# LEDPanel_Dimmer.net
KiCad netlist of a schematic drawn in EAGLE
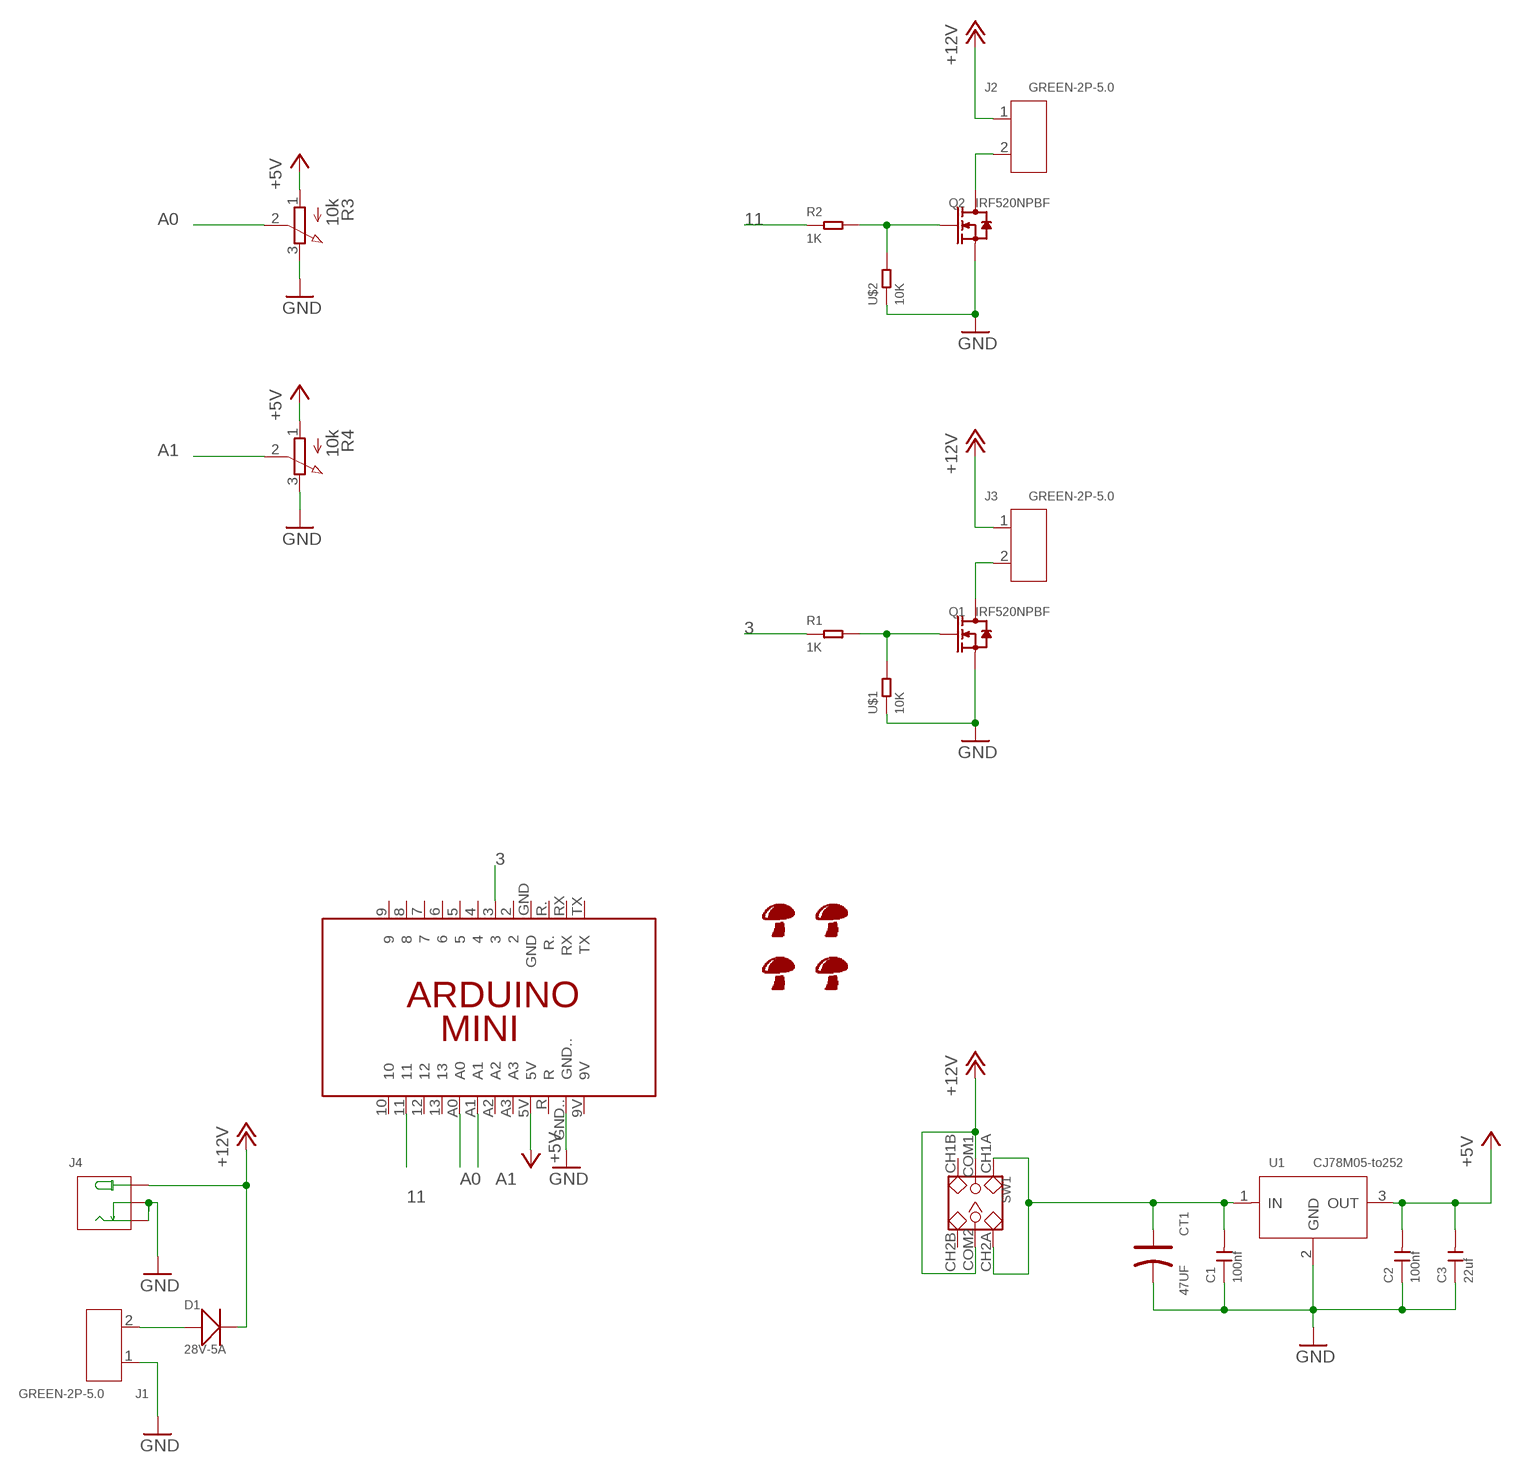
[diagram p0: schematic, sheet 1]

(export (version "E")
  (design (tool "Eeschema 10.0.6"))
  (components
    (comp (ref "C1")
      (value "100nf")
      (footprint "eagle-import:C0805")
      (fields (field (name "MPN") "CC0805KRX7R9BB104"))
      (libsource (lib "eagle-import") (part "CERAMIC-100NF-50V-10%-X7R(0805)"))
    )
    (comp (ref "C2")
      (value "100nf")
      (footprint "eagle-import:C0805")
      (fields (field (name "MPN") "CC0805KRX7R9BB104"))
      (libsource (lib "eagle-import") (part "CERAMIC-100NF-50V-10%-X7R(0805)"))
    )
    (comp (ref "C3")
      (value "22uf")
      (footprint "eagle-import:C0805")
      (fields (field (name "MPN") "CC0805MKX5R5BB226"))
      (libsource (lib "eagle-import") (part "CERAMIC-22UF-6.3V-20%-X5R(0805)"))
    )
    (comp (ref "CT1")
      (value "47UF")
      (footprint "eagle-import:ELECTRO-SMD-C-6MM")
      (fields (field (name "MPN") "CS1E470M-CRE54"))
      (libsource (lib "eagle-import") (part "ALUMINUM-SMD-47UF-25V(D6.3-H5.3MM)"))
    )
    (comp (ref "D1")
      (value "28V-5A")
      (footprint "eagle-import:DO-214AA")
      (fields (field (name "MPN") "SS54B"))
      (libsource (lib "eagle-import") (part "SMD-DIODE-SCHOTTKY-28V-5A(DO-214AA)"))
    )
    (comp (ref "J1")
      (value "GREEN-2P-5.0")
      (footprint "eagle-import:H2-5.0-10.5X8.0MM")
      (libsource (lib "eagle-import") (part "SCREW-TERMINAL-GREEN(2P-5.0)"))
    )
    (comp (ref "J2")
      (value "GREEN-2P-5.0")
      (footprint "eagle-import:H2-5.0-10.5X8.0MM")
      (libsource (lib "eagle-import") (part "SCREW-TERMINAL-GREEN(2P-5.0)"))
    )
    (comp (ref "J3")
      (value "GREEN-2P-5.0")
      (footprint "eagle-import:H2-5.0-10.5X8.0MM")
      (libsource (lib "eagle-import") (part "SCREW-TERMINAL-GREEN(2P-5.0)"))
    )
    (comp (ref "J4")
      (value "JACK-DC-005'DC-005'")
      (footprint "eagle-import:3P-L14.2_W11.0_H9.0MM")
      (libsource (lib "eagle-import") (part "JACK-DC-005'DC-005'"))
    )
    (comp (ref "Q1")
      (value "IRF520NPBF")
      (footprint "eagle-import:TO-220")
      (libsource (lib "eagle-import") (part "DIP-MOSFET-N-CH-100V-9.7A-IRF520NPBF(TO-220AB)"))
    )
    (comp (ref "Q2")
      (value "IRF520NPBF")
      (footprint "eagle-import:TO-220")
      (libsource (lib "eagle-import") (part "DIP-MOSFET-N-CH-100V-9.7A-IRF520NPBF(TO-220AB)"))
    )
    (comp (ref "R1")
      (value "1K")
      (footprint "eagle-import:R0805")
      (fields (field (name "MPN") "RC0805JR-071KL"))
      (libsource (lib "eagle-import") (part "SMD-RES-100R-1%-1/8W(0805)"))
    )
    (comp (ref "R2")
      (value "1K")
      (footprint "eagle-import:R0805")
      (fields (field (name "MPN") "RC0805JR-071KL"))
      (libsource (lib "eagle-import") (part "SMD-RES-100R-1%-1/8W(0805)"))
    )
    (comp (ref "R3")
      (value "10k")
      (footprint "eagle-import:3RP_1610N")
      (libsource (lib "eagle-import") (part "3RP/1610N"))
    )
    (comp (ref "R4")
      (value "10k")
      (footprint "eagle-import:3RP_1610N")
      (libsource (lib "eagle-import") (part "3RP/1610N"))
    )
    (comp (ref "SW1")
      (value "DIP-TOGGLE-SWITCH-2CH-(2X3P-2.54)")
      (footprint "eagle-import:SW6-2.54-9.0X3.5X3.2+2.0MM")
      (fields (field (name "MPN") "MS-22D18 G2 ROHS"))
      (libsource (lib "eagle-import") (part "DIP-TOGGLE-SWITCH-2CH-(2X3P-2.54)"))
    )
    (comp (ref "U$1")
      (value "10K")
      (footprint "eagle-import:R0805")
      (fields (field (name "MPN") "RC0805FR-0710KL"))
      (libsource (lib "eagle-import") (part "SMD-RES-10K-1%-1/8W(0805)"))
    )
    (comp (ref "U$2")
      (value "10K")
      (footprint "eagle-import:R0805")
      (fields (field (name "MPN") "RC0805FR-0710KL"))
      (libsource (lib "eagle-import") (part "SMD-RES-10K-1%-1/8W(0805)"))
    )
    (comp (ref "U$3")
      (value "ARDUINO_MINI_REDUCED")
      (footprint "eagle-import:ARDUINO_MINI_REDUCED")
      (libsource (lib "eagle-import") (part "ARDUINO_MINI_REDUCED"))
    )
    (comp (ref "U$4")
      (value "SHROOMBOTTOMSILK")
      (footprint "eagle-import:SHROOM_BS")
      (libsource (lib "eagle-import") (part "SHROOMBOTTOMSILK"))
    )
    (comp (ref "U$5")
      (value "SHROOMTOPSILK")
      (footprint "eagle-import:SHROOM_TS")
      (libsource (lib "eagle-import") (part "SHROOMTOPSILK"))
    )
    (comp (ref "U$6")
      (value "SHROOM10MM")
      (footprint "eagle-import:SHROOM10MM")
      (libsource (lib "eagle-import") (part "SHROOM10MM"))
    )
    (comp (ref "U$7")
      (value "SHROOM5MM")
      (footprint "eagle-import:SHROOM")
      (libsource (lib "eagle-import") (part "SHROOM5MM"))
    )
    (comp (ref "U1")
      (value "CJ78M05-to252")
      (footprint "eagle-import:TO-252")
      (fields (field (name "MPN") "CJ78M05"))
      (libsource (lib "eagle-import") (part "PMIC-CJ78M05(TO-252)"))
    )
  )
  (nets
    (net (code "1") (name "+5V") (class "Default")
      (node (ref "C2") (pin "2") (pinfunction "2_2") (pintype "passive"))
      (node (ref "C3") (pin "2") (pinfunction "2_2") (pintype "passive"))
      (node (ref "R3") (pin "1") (pinfunction "A_1") (pintype "passive"))
      (node (ref "R4") (pin "1") (pinfunction "A_1") (pintype "passive"))
      (node (ref "U$3") (pin "5V") (pinfunction "5V_5V") (pintype "bidirectional"))
      (node (ref "U1") (pin "3") (pinfunction "OUT_3") (pintype "bidirectional"))
    )
    (net (code "2") (name "+12V") (class "Default")
      (node (ref "D1") (pin "-") (pinfunction "-_-") (pintype "passive"))
      (node (ref "J2") (pin "1") (pinfunction "1_1") (pintype "bidirectional"))
      (node (ref "J3") (pin "1") (pinfunction "1_1") (pintype "bidirectional"))
      (node (ref "J4") (pin "+") (pinfunction "+_+") (pintype "bidirectional"))
      (node (ref "SW1") (pin "COM1") (pinfunction "COM1_COM1") (pintype "bidirectional"))
      (node (ref "SW1") (pin "COM2") (pinfunction "COM2_COM2") (pintype "bidirectional"))
    )
    (net (code "3") (name "/3") (class "Default")
      (node (ref "R1") (pin "1") (pinfunction "1_1") (pintype "passive"))
      (node (ref "U$3") (pin "3") (pinfunction "3_3") (pintype "bidirectional"))
    )
    (net (code "4") (name "/11") (class "Default")
      (node (ref "R2") (pin "1") (pinfunction "1_1") (pintype "passive"))
      (node (ref "U$3") (pin "11") (pinfunction "11_11") (pintype "bidirectional"))
    )
    (net (code "5") (name "/A0") (class "Default")
      (node (ref "R3") (pin "2") (pinfunction "S_2") (pintype "passive"))
      (node (ref "U$3") (pin "A0") (pinfunction "A0_A0") (pintype "bidirectional"))
    )
    (net (code "6") (name "/A1") (class "Default")
      (node (ref "R4") (pin "2") (pinfunction "S_2") (pintype "passive"))
      (node (ref "U$3") (pin "A1") (pinfunction "A1_A1") (pintype "bidirectional"))
    )
    (net (code "7") (name "GND") (class "Default")
      (node (ref "C1") (pin "1") (pinfunction "1_1") (pintype "passive"))
      (node (ref "C2") (pin "1") (pinfunction "1_1") (pintype "passive"))
      (node (ref "C3") (pin "1") (pinfunction "1_1") (pintype "passive"))
      (node (ref "CT1") (pin "-") (pinfunction "-_-") (pintype "passive"))
      (node (ref "J1") (pin "1") (pinfunction "1_1") (pintype "bidirectional"))
      (node (ref "J4") (pin "-1") (pinfunction "-_-1") (pintype "bidirectional"))
      (node (ref "J4") (pin "-2") (pinfunction "CDN_-2") (pintype "bidirectional"))
      (node (ref "Q1") (pin "3") (pinfunction "S_3") (pintype "passive"))
      (node (ref "Q2") (pin "3") (pinfunction "S_3") (pintype "passive"))
      (node (ref "R3") (pin "3") (pinfunction "E_3") (pintype "passive"))
      (node (ref "R4") (pin "3") (pinfunction "E_3") (pintype "passive"))
      (node (ref "U$1") (pin "1") (pinfunction "1_1") (pintype "passive"))
      (node (ref "U$2") (pin "1") (pinfunction "1_1") (pintype "passive"))
      (node (ref "U$3") (pin "GND..") (pinfunction "GND.._GND..") (pintype "bidirectional"))
      (node (ref "U1") (pin "2") (pinfunction "GND_2") (pintype "bidirectional"))
    )
    (net (code "8") (name "Net-(D1-Pad+)") (class "Default")
      (node (ref "D1") (pin "+") (pinfunction "+_+") (pintype "passive"))
      (node (ref "J1") (pin "2") (pinfunction "2_2") (pintype "bidirectional"))
    )
    (net (code "9") (name "Net-(J2-Pad2)") (class "Default")
      (node (ref "J2") (pin "2") (pinfunction "2_2") (pintype "bidirectional"))
      (node (ref "Q2") (pin "2") (pinfunction "D_2") (pintype "passive"))
      (node (ref "Q2") (pin "HEAT") (pinfunction "D_HEAT") (pintype "passive"))
    )
    (net (code "10") (name "Net-(J3-Pad2)") (class "Default")
      (node (ref "J3") (pin "2") (pinfunction "2_2") (pintype "bidirectional"))
      (node (ref "Q1") (pin "2") (pinfunction "D_2") (pintype "passive"))
      (node (ref "Q1") (pin "HEAT") (pinfunction "D_HEAT") (pintype "passive"))
    )
    (net (code "11") (name "Net-(Q1-G)") (class "Default")
      (node (ref "Q1") (pin "1") (pinfunction "G_1") (pintype "passive"))
      (node (ref "R1") (pin "2") (pinfunction "2_2") (pintype "passive"))
      (node (ref "U$1") (pin "2") (pinfunction "2_2") (pintype "passive"))
    )
    (net (code "12") (name "Net-(Q2-G)") (class "Default")
      (node (ref "Q2") (pin "1") (pinfunction "G_1") (pintype "passive"))
      (node (ref "R2") (pin "2") (pinfunction "2_2") (pintype "passive"))
      (node (ref "U$2") (pin "2") (pinfunction "2_2") (pintype "passive"))
    )
    (net (code "13") (name "Net-(U1-IN)") (class "Default")
      (node (ref "C1") (pin "2") (pinfunction "2_2") (pintype "passive"))
      (node (ref "CT1") (pin "+") (pinfunction "+_+") (pintype "passive"))
      (node (ref "SW1") (pin "CH1A") (pinfunction "CH1A_CH1A") (pintype "bidirectional"))
      (node (ref "SW1") (pin "CH2A") (pinfunction "CH2A_CH2A") (pintype "bidirectional"))
      (node (ref "U1") (pin "1") (pinfunction "IN_1") (pintype "bidirectional"))
    )
    (net (code "14") (name "unconnected-(SW1-PadCH1B)") (class "Default")
      (node (ref "SW1") (pin "CH1B") (pinfunction "CH1B_CH1B") (pintype "bidirectional"))
    )
    (net (code "15") (name "unconnected-(SW1-PadCH2B)") (class "Default")
      (node (ref "SW1") (pin "CH2B") (pinfunction "CH2B_CH2B") (pintype "bidirectional"))
    )
    (net (code "16") (name "unconnected-(U$3-Pad2)") (class "Default")
      (node (ref "U$3") (pin "2") (pinfunction "2_2") (pintype "bidirectional"))
    )
    (net (code "17") (name "unconnected-(U$3-Pad4)") (class "Default")
      (node (ref "U$3") (pin "4") (pinfunction "4_4") (pintype "bidirectional"))
    )
    (net (code "18") (name "unconnected-(U$3-Pad5)") (class "Default")
      (node (ref "U$3") (pin "5") (pinfunction "5_5") (pintype "bidirectional"))
    )
    (net (code "19") (name "unconnected-(U$3-Pad6)") (class "Default")
      (node (ref "U$3") (pin "6") (pinfunction "6_6") (pintype "bidirectional"))
    )
    (net (code "20") (name "unconnected-(U$3-Pad7)") (class "Default")
      (node (ref "U$3") (pin "7") (pinfunction "7_7") (pintype "bidirectional"))
    )
    (net (code "21") (name "unconnected-(U$3-Pad8)") (class "Default")
      (node (ref "U$3") (pin "8") (pinfunction "8_8") (pintype "bidirectional"))
    )
    (net (code "22") (name "unconnected-(U$3-Pad9)") (class "Default")
      (node (ref "U$3") (pin "9") (pinfunction "9_9") (pintype "bidirectional"))
    )
    (net (code "23") (name "unconnected-(U$3-Pad9V)") (class "Default")
      (node (ref "U$3") (pin "9V") (pinfunction "9V_9V") (pintype "bidirectional"))
    )
    (net (code "24") (name "unconnected-(U$3-Pad10)") (class "Default")
      (node (ref "U$3") (pin "10") (pinfunction "10_10") (pintype "bidirectional"))
    )
    (net (code "25") (name "unconnected-(U$3-Pad12)") (class "Default")
      (node (ref "U$3") (pin "12") (pinfunction "12_12") (pintype "bidirectional"))
    )
    (net (code "26") (name "unconnected-(U$3-Pad13)") (class "Default")
      (node (ref "U$3") (pin "13") (pinfunction "13_13") (pintype "bidirectional"))
    )
    (net (code "27") (name "unconnected-(U$3-PadA2)") (class "Default")
      (node (ref "U$3") (pin "A2") (pinfunction "A2_A2") (pintype "bidirectional"))
    )
    (net (code "28") (name "unconnected-(U$3-PadA3)") (class "Default")
      (node (ref "U$3") (pin "A3") (pinfunction "A3_A3") (pintype "bidirectional"))
    )
    (net (code "29") (name "unconnected-(U$3-PadGND)") (class "Default")
      (node (ref "U$3") (pin "GND") (pinfunction "GND_GND") (pintype "bidirectional"))
    )
    (net (code "30") (name "unconnected-(U$3-PadR)") (class "Default")
      (node (ref "U$3") (pin "R") (pinfunction "R_R") (pintype "bidirectional"))
    )
    (net (code "31") (name "unconnected-(U$3-PadR.)") (class "Default")
      (node (ref "U$3") (pin "R.") (pinfunction "R._R.") (pintype "bidirectional"))
    )
    (net (code "32") (name "unconnected-(U$3-PadRX)") (class "Default")
      (node (ref "U$3") (pin "RX") (pinfunction "RX_RX") (pintype "bidirectional"))
    )
    (net (code "33") (name "unconnected-(U$3-PadTX)") (class "Default")
      (node (ref "U$3") (pin "TX") (pinfunction "TX_TX") (pintype "bidirectional"))
    )
  )
)
